# Base.net
KiCad netlist of a schematic drawn in EAGLE
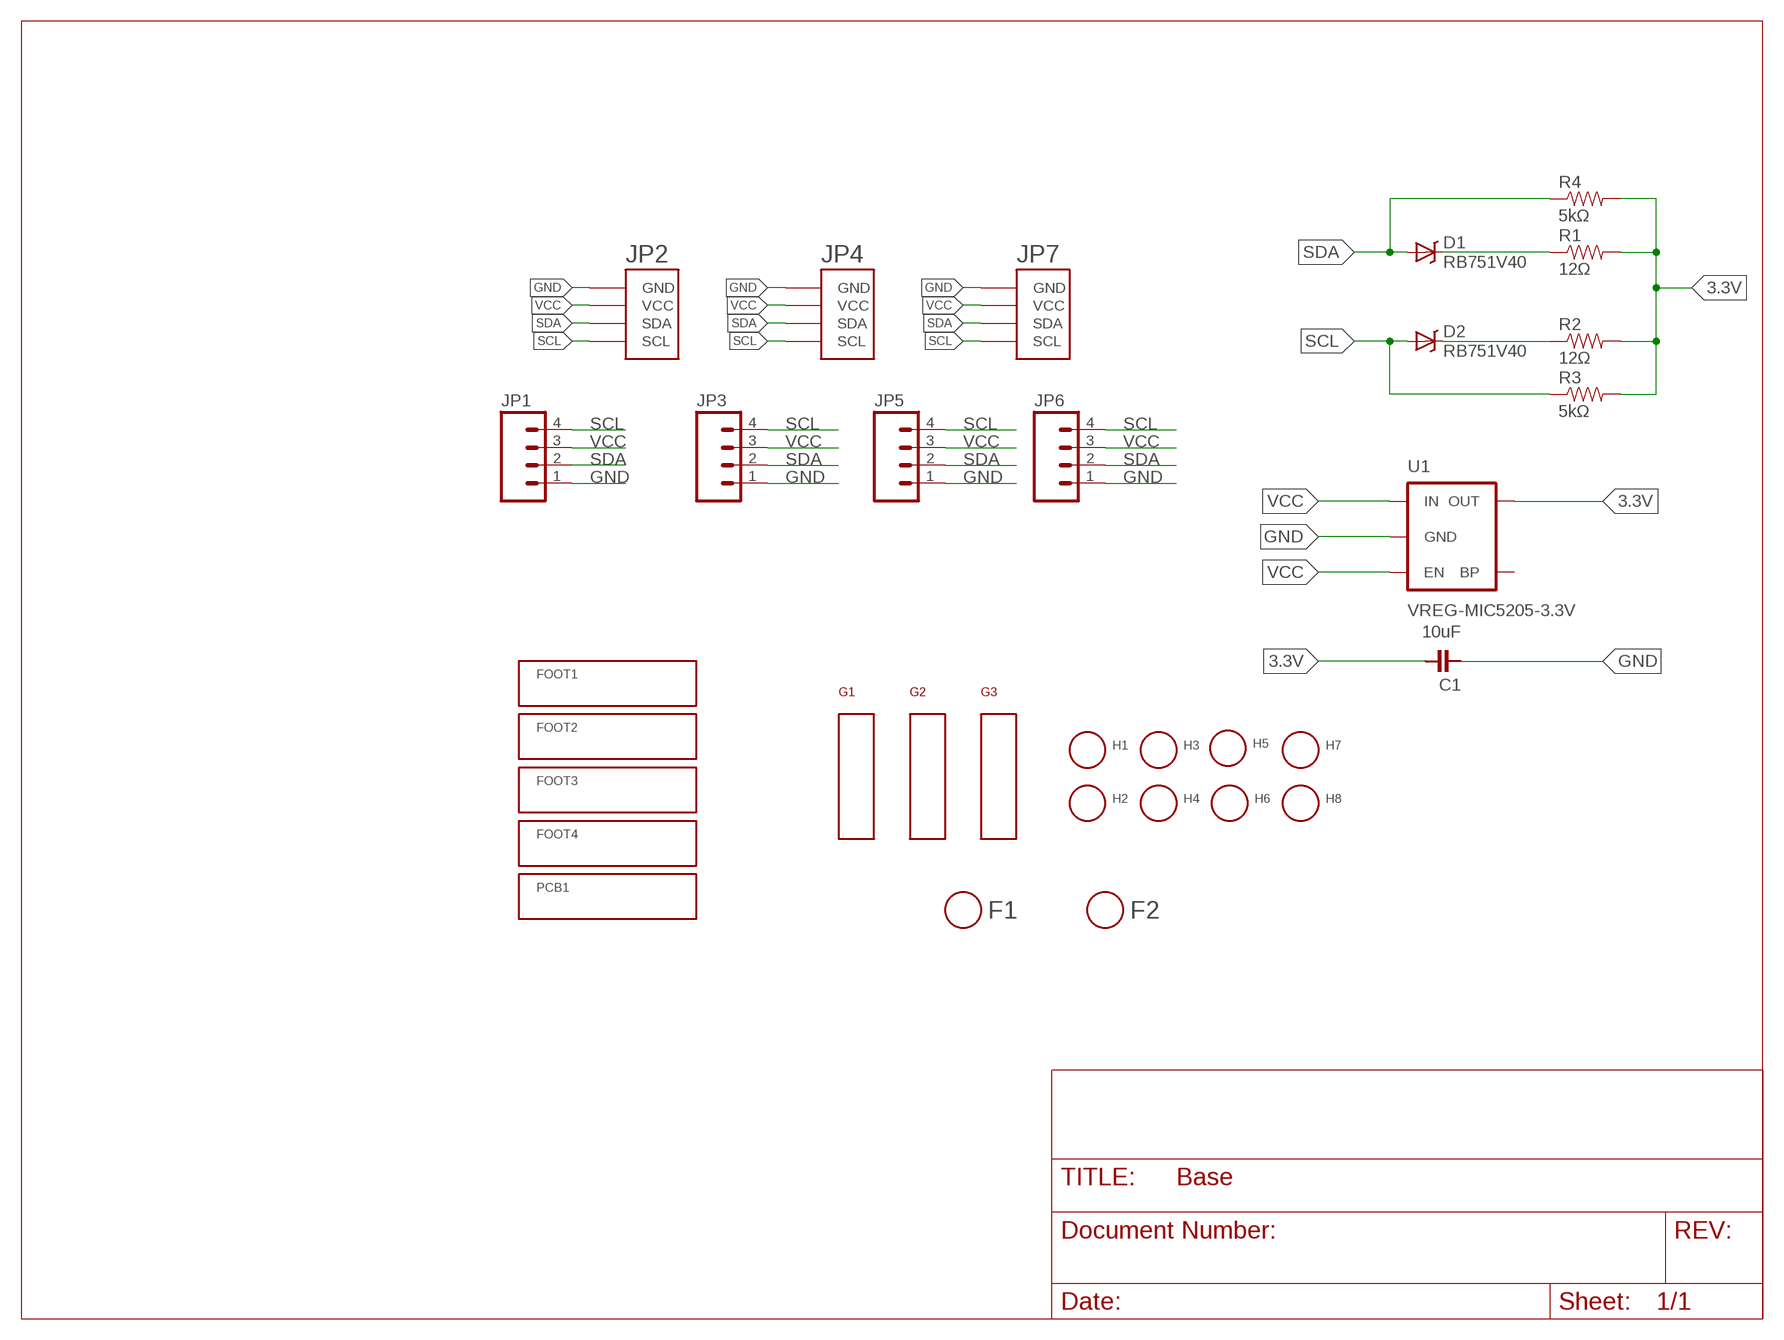
[diagram p0: schematic, sheet 1]

(export (version "E")
  (design (tool "Eeschema 10.0.6"))
  (components
    (comp (ref "C1")
      (value "10uF")
      (footprint "eagle-import:0603")
      (fields (field (name "PARTNUM") "GRM188R61C106MA73D"))
      (libsource (lib "eagle-import") (part "CAPACITOR-10UF"))
    )
    (comp (ref "D1")
      (value "RB751V40")
      (footprint "eagle-import:SOD-323")
      (fields (field (name "PARTNUM") "BAT60A") (field (name "PARTNUM_1") "RB751V40"))
      (libsource (lib "eagle-import") (part "DIODE-SCHOTTKY-BAT60A"))
    )
    (comp (ref "D2")
      (value "RB751V40")
      (footprint "eagle-import:SOD-323")
      (fields (field (name "PARTNUM") "BAT60A") (field (name "PARTNUM_1") "RB751V40"))
      (libsource (lib "eagle-import") (part "DIODE-SCHOTTKY-BAT60A"))
    )
    (comp (ref "F1")
      (value "FIDUCIAL")
      (footprint "eagle-import:FIDUCIAL_1MM")
      (libsource (lib "eagle-import") (part "FIDUCIAL"))
    )
    (comp (ref "F2")
      (value "FIDUCIAL")
      (footprint "eagle-import:FIDUCIAL_1MM")
      (libsource (lib "eagle-import") (part "FIDUCIAL"))
    )
    (comp (ref "G1")
      (value "CARD-GUIDE")
      (footprint "eagle-import:CARD-GUIDE-2")
      (fields (field (name "PARTNUM") "HCG-201-165"))
      (libsource (lib "eagle-import") (part "CARD-GUIDE"))
    )
    (comp (ref "G2")
      (value "CARD-GUIDE")
      (footprint "eagle-import:CARD-GUIDE-2")
      (fields (field (name "PARTNUM") "HCG-202-165"))
      (libsource (lib "eagle-import") (part "CARD-GUIDE"))
    )
    (comp (ref "G3")
      (value "CARD-GUIDE")
      (footprint "eagle-import:CARD-GUIDE-2")
      (fields (field (name "PARTNUM") "HCG-201-165"))
      (libsource (lib "eagle-import") (part "CARD-GUIDE"))
    )
    (comp (ref "H1")
      (value "HOLE#2")
      (footprint "eagle-import:HOLE-#2")
      (fields (field (name "PARTNUM") "EXCLUDE"))
      (libsource (lib "eagle-import") (part "HOLE#2"))
    )
    (comp (ref "H2")
      (value "HOLE#2")
      (footprint "eagle-import:HOLE-#2")
      (fields (field (name "PARTNUM") "EXCLUDE"))
      (libsource (lib "eagle-import") (part "HOLE#2"))
    )
    (comp (ref "H3")
      (value "HOLE#2")
      (footprint "eagle-import:HOLE-#2")
      (fields (field (name "PARTNUM") "EXCLUDE"))
      (libsource (lib "eagle-import") (part "HOLE#2"))
    )
    (comp (ref "H4")
      (value "HOLE#2")
      (footprint "eagle-import:HOLE-#2")
      (fields (field (name "PARTNUM") "EXCLUDE"))
      (libsource (lib "eagle-import") (part "HOLE#2"))
    )
    (comp (ref "H5")
      (value "HOLE#2")
      (footprint "eagle-import:HOLE-#2")
      (fields (field (name "PARTNUM") "EXCLUDE"))
      (libsource (lib "eagle-import") (part "HOLE#2"))
    )
    (comp (ref "H6")
      (value "HOLE#2")
      (footprint "eagle-import:HOLE-#2")
      (fields (field (name "PARTNUM") "EXCLUDE"))
      (libsource (lib "eagle-import") (part "HOLE#2"))
    )
    (comp (ref "H7")
      (value "HOLE#2")
      (footprint "eagle-import:HOLE-#2")
      (fields (field (name "PARTNUM") "EXCLUDE"))
      (libsource (lib "eagle-import") (part "HOLE#2"))
    )
    (comp (ref "H8")
      (value "HOLE#2")
      (footprint "eagle-import:HOLE-#2")
      (fields (field (name "PARTNUM") "EXCLUDE"))
      (libsource (lib "eagle-import") (part "HOLE#2"))
    )
    (comp (ref "JP1")
      (value "M04LOCK")
      (footprint "eagle-import:1X04_LOCK")
      (fields (field (name "PARTNUM") "M20-9750446"))
      (libsource (lib "eagle-import") (part "M04LOCK"))
    )
    (comp (ref "JP2")
      (value "HEADER-MODULO")
      (footprint "eagle-import:JST-PA-SIDE-SMD")
      (fields (field (name "PARTNUM") "4P-SMD-2.0-90D"))
      (libsource (lib "eagle-import") (part "HEADER-MODULO"))
    )
    (comp (ref "JP3")
      (value "M04LOCK")
      (footprint "eagle-import:1X04_LOCK")
      (fields (field (name "PARTNUM") "M20-9750446"))
      (libsource (lib "eagle-import") (part "M04LOCK"))
    )
    (comp (ref "JP4")
      (value "HEADER-MODULO")
      (footprint "eagle-import:JST-PA-SIDE-SMD")
      (fields (field (name "PARTNUM") "4P-SMD-2.0-90D"))
      (libsource (lib "eagle-import") (part "HEADER-MODULO"))
    )
    (comp (ref "JP5")
      (value "M04LOCK")
      (footprint "eagle-import:1X04_LOCK")
      (fields (field (name "PARTNUM") "M20-9750446"))
      (libsource (lib "eagle-import") (part "M04LOCK"))
    )
    (comp (ref "JP6")
      (value "M04LOCK")
      (footprint "eagle-import:1X04_LOCK")
      (fields (field (name "PARTNUM") "M20-9750446"))
      (libsource (lib "eagle-import") (part "M04LOCK"))
    )
    (comp (ref "JP7")
      (value "HEADER-MODULO")
      (footprint "eagle-import:JST-PA-SIDE-SMD")
      (fields (field (name "PARTNUM") "4P-SMD-2.0-90D"))
      (libsource (lib "eagle-import") (part "HEADER-MODULO"))
    )
    (comp (ref "R1")
      (value "12Ω")
      (footprint "eagle-import:0603")
      (fields (field (name "PARTNUM") "ERJ-PA3J120V"))
      (libsource (lib "eagle-import") (part "RESISTOR-12Ω"))
    )
    (comp (ref "R2")
      (value "12Ω")
      (footprint "eagle-import:0603")
      (fields (field (name "PARTNUM") "ERJ-PA3J120V"))
      (libsource (lib "eagle-import") (part "RESISTOR-12Ω"))
    )
    (comp (ref "R3")
      (value "5kΩ")
      (footprint "eagle-import:0603")
      (fields (field (name "PARTNUM") "ERJ-3EKF5101V"))
      (libsource (lib "eagle-import") (part "RESISTOR-5KΩ"))
    )
    (comp (ref "R4")
      (value "5kΩ")
      (footprint "eagle-import:0603")
      (fields (field (name "PARTNUM") "ERJ-3EKF5101V"))
      (libsource (lib "eagle-import") (part "RESISTOR-5KΩ"))
    )
    (comp (ref "U1")
      (value "VREG-MIC5205-3.3V")
      (footprint "eagle-import:SOT23-5")
      (fields (field (name "PARTNUM") "MIC5205-3.3YM5 TR"))
      (libsource (lib "eagle-import") (part "VREG-MIC5205-3.3V"))
    )
  )
  (nets
    (net (code "1") (name "3.3V") (class "Default")
      (node (ref "C1") (pin "1") (pinfunction "1_1") (pintype "passive"))
      (node (ref "R1") (pin "2") (pinfunction "2_2") (pintype "passive"))
      (node (ref "R2") (pin "2") (pinfunction "2_2") (pintype "passive"))
      (node (ref "R3") (pin "2") (pinfunction "2_2") (pintype "passive"))
      (node (ref "R4") (pin "2") (pinfunction "2_2") (pintype "passive"))
      (node (ref "U1") (pin "5") (pinfunction "OUT_5") (pintype "passive"))
    )
    (net (code "2") (name "GND") (class "Default")
      (node (ref "C1") (pin "2") (pinfunction "2_2") (pintype "passive"))
      (node (ref "JP1") (pin "1") (pinfunction "1_1") (pintype "passive"))
      (node (ref "JP2") (pin "1") (pinfunction "GND_1") (pintype "bidirectional"))
      (node (ref "JP3") (pin "1") (pinfunction "1_1") (pintype "passive"))
      (node (ref "JP4") (pin "1") (pinfunction "GND_1") (pintype "bidirectional"))
      (node (ref "JP5") (pin "1") (pinfunction "1_1") (pintype "passive"))
      (node (ref "JP6") (pin "1") (pinfunction "1_1") (pintype "passive"))
      (node (ref "JP7") (pin "1") (pinfunction "GND_1") (pintype "bidirectional"))
      (node (ref "U1") (pin "2") (pinfunction "GND_2") (pintype "input"))
    )
    (net (code "3") (name "Net-(D1-PadC)") (class "Default")
      (node (ref "D1") (pin "C") (pinfunction "C_C") (pintype "passive"))
      (node (ref "R1") (pin "1") (pinfunction "1_1") (pintype "passive"))
    )
    (net (code "4") (name "Net-(D2-PadC)") (class "Default")
      (node (ref "D2") (pin "C") (pinfunction "C_C") (pintype "passive"))
      (node (ref "R2") (pin "1") (pinfunction "1_1") (pintype "passive"))
    )
    (net (code "5") (name "SCL") (class "Default")
      (node (ref "D2") (pin "A") (pinfunction "A_A") (pintype "passive"))
      (node (ref "JP1") (pin "4") (pinfunction "4_4") (pintype "passive"))
      (node (ref "JP2") (pin "4") (pinfunction "SCL_4") (pintype "bidirectional"))
      (node (ref "JP3") (pin "4") (pinfunction "4_4") (pintype "passive"))
      (node (ref "JP4") (pin "4") (pinfunction "SCL_4") (pintype "bidirectional"))
      (node (ref "JP5") (pin "4") (pinfunction "4_4") (pintype "passive"))
      (node (ref "JP6") (pin "4") (pinfunction "4_4") (pintype "passive"))
      (node (ref "JP7") (pin "4") (pinfunction "SCL_4") (pintype "bidirectional"))
      (node (ref "R3") (pin "1") (pinfunction "1_1") (pintype "passive"))
    )
    (net (code "6") (name "SDA") (class "Default")
      (node (ref "D1") (pin "A") (pinfunction "A_A") (pintype "passive"))
      (node (ref "JP1") (pin "2") (pinfunction "2_2") (pintype "passive"))
      (node (ref "JP2") (pin "3") (pinfunction "SDA_3") (pintype "bidirectional"))
      (node (ref "JP3") (pin "2") (pinfunction "2_2") (pintype "passive"))
      (node (ref "JP4") (pin "3") (pinfunction "SDA_3") (pintype "bidirectional"))
      (node (ref "JP5") (pin "2") (pinfunction "2_2") (pintype "passive"))
      (node (ref "JP6") (pin "2") (pinfunction "2_2") (pintype "passive"))
      (node (ref "JP7") (pin "3") (pinfunction "SDA_3") (pintype "bidirectional"))
      (node (ref "R4") (pin "1") (pinfunction "1_1") (pintype "passive"))
    )
    (net (code "7") (name "VCC") (class "Default")
      (node (ref "JP1") (pin "3") (pinfunction "3_3") (pintype "passive"))
      (node (ref "JP2") (pin "2") (pinfunction "VCC_2") (pintype "bidirectional"))
      (node (ref "JP3") (pin "3") (pinfunction "3_3") (pintype "passive"))
      (node (ref "JP4") (pin "2") (pinfunction "VCC_2") (pintype "bidirectional"))
      (node (ref "JP5") (pin "3") (pinfunction "3_3") (pintype "passive"))
      (node (ref "JP6") (pin "3") (pinfunction "3_3") (pintype "passive"))
      (node (ref "JP7") (pin "2") (pinfunction "VCC_2") (pintype "bidirectional"))
      (node (ref "U1") (pin "1") (pinfunction "IN_1") (pintype "input"))
      (node (ref "U1") (pin "3") (pinfunction "EN_3") (pintype "input"))
    )
    (net (code "8") (name "unconnected-(H1-HOLE-PadP$1)") (class "Default")
      (node (ref "H1") (pin "P$1") (pinfunction "HOLE_P$1") (pintype "bidirectional"))
    )
    (net (code "9") (name "unconnected-(H2-HOLE-PadP$1)") (class "Default")
      (node (ref "H2") (pin "P$1") (pinfunction "HOLE_P$1") (pintype "bidirectional"))
    )
    (net (code "10") (name "unconnected-(H3-HOLE-PadP$1)") (class "Default")
      (node (ref "H3") (pin "P$1") (pinfunction "HOLE_P$1") (pintype "bidirectional"))
    )
    (net (code "11") (name "unconnected-(H4-HOLE-PadP$1)") (class "Default")
      (node (ref "H4") (pin "P$1") (pinfunction "HOLE_P$1") (pintype "bidirectional"))
    )
    (net (code "12") (name "unconnected-(H5-HOLE-PadP$1)") (class "Default")
      (node (ref "H5") (pin "P$1") (pinfunction "HOLE_P$1") (pintype "bidirectional"))
    )
    (net (code "13") (name "unconnected-(H6-HOLE-PadP$1)") (class "Default")
      (node (ref "H6") (pin "P$1") (pinfunction "HOLE_P$1") (pintype "bidirectional"))
    )
    (net (code "14") (name "unconnected-(H7-HOLE-PadP$1)") (class "Default")
      (node (ref "H7") (pin "P$1") (pinfunction "HOLE_P$1") (pintype "bidirectional"))
    )
    (net (code "15") (name "unconnected-(H8-HOLE-PadP$1)") (class "Default")
      (node (ref "H8") (pin "P$1") (pinfunction "HOLE_P$1") (pintype "bidirectional"))
    )
    (net (code "16") (name "unconnected-(U1-BP-Pad4)") (class "Default")
      (node (ref "U1") (pin "4") (pinfunction "BP_4") (pintype "input"))
    )
  )
)
